# DCDC_stepdown.net
KiCad netlist of a schematic drawn in Altium Designer
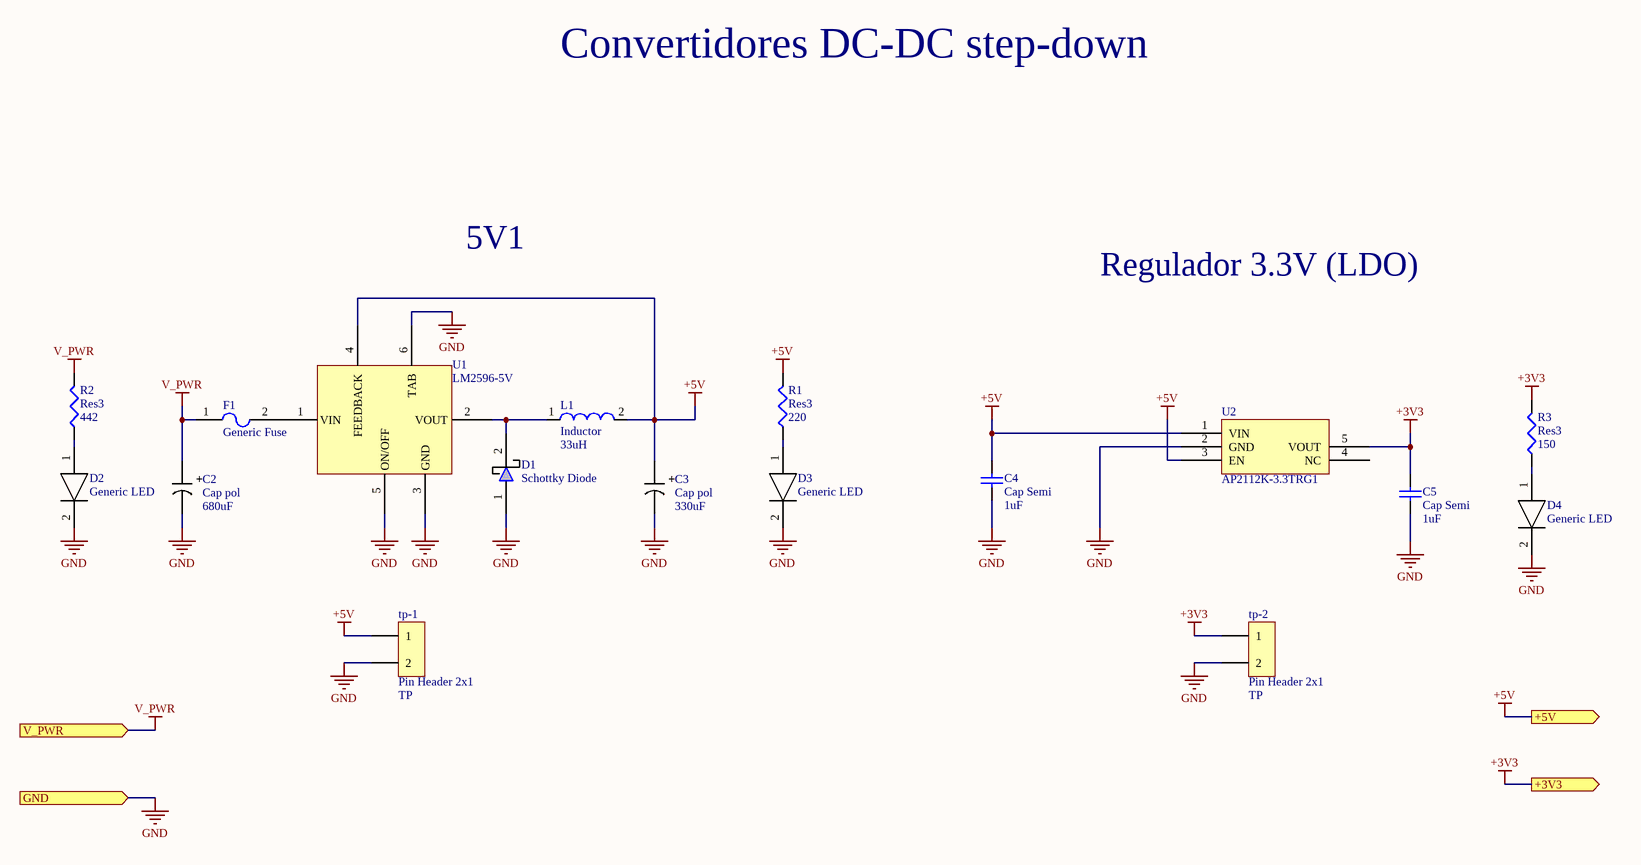
[diagram p0: DCDC_stepdown.SchDoc]

(export (version "E")
  (design (tool "Eeschema 10.0.6"))
  (components
    (comp (ref "C2")
      (value "Cap pol")
      (footprint "CAP_SMD_Electrolytic_10x10")
      (description "Electrolytic Aluminium Capacitor")
      (fields
        (field (name "MANUFACTURER") "PANASONIC")
        (field (name "MANUFACTURER PART NUMBER") "EEEFK1V681AQ")
        (field (name "ALTIUM_VALUE") "680uF")
      )
      (libsource (lib "IoWLabs") (part "Cap pol"))
    )
    (comp (ref "C3")
      (value "Cap pol")
      (footprint "CAP_SMD_Electrolytic_10x10")
      (description "Electrolytic Aluminium Capacitor")
      (fields
        (field (name "MANUFACTURER") "PANASONIC")
        (field (name "MANUFACTURER PART NUMBER") "EEE1VA331UAP")
        (field (name "ALTIUM_VALUE") "330uF")
      )
      (libsource (lib "IoWLabs") (part "Cap pol"))
    )
    (comp (ref "C4")
      (value "Cap Semi")
      (footprint "1608[0603]")
      (description "Capacitor (Semiconductor SIM Model)")
      (fields
        (field (name "ALTIUM_VALUE") "1uF")
        (field (name "MANUFACTURER") "Samsung Electro-Mechanics")
        (field (name "MANUFACTURER PART NUMBER") "CL10B105KO8NNNC")
        (field (name "PUBLISHER") "Altium Limited")
      )
      (libsource (lib "Miscellaneous Devices") (part "Cap Semi"))
    )
    (comp (ref "C5")
      (value "Cap Semi")
      (footprint "1608[0603]")
      (description "Capacitor (Semiconductor SIM Model)")
      (fields
        (field (name "ALTIUM_VALUE") "1uF")
        (field (name "MANUFACTURER") "Samsung Electro-Mechanics")
        (field (name "MANUFACTURER PART NUMBER") "CL10B105KO8NNNC")
        (field (name "PUBLISHER") "Altium Limited")
      )
      (libsource (lib "Miscellaneous Devices") (part "Cap Semi"))
    )
    (comp (ref "D1")
      (value "Schottky Diode")
      (footprint "SMB_L4.6-W3.6-LS5.3-RD")
      (description "Schottky Diodes")
      (fields
        (field (name "MANUFACTURER") "MCC(Micro Commercial Components)")
        (field (name "MANUFACTURER PART NUMBER") "SK32B-LTP")
      )
      (libsource (lib "IoWLabs") (part "Schottky Diode"))
    )
    (comp (ref "D2")
      (value "Generic LED")
      (footprint "LED0603")
      (description "Generic LED SMD")
      (libsource (lib "IoWLabs") (part "LED"))
    )
    (comp (ref "D3")
      (value "Generic LED")
      (footprint "LED0603")
      (description "Generic LED SMD")
      (libsource (lib "IoWLabs") (part "LED"))
    )
    (comp (ref "D4")
      (value "Generic LED")
      (footprint "LED0603")
      (description "Generic LED SMD")
      (libsource (lib "IoWLabs") (part "LED"))
    )
    (comp (ref "F1")
      (value "Generic Fuse")
      (footprint "F1206")
      (description "SMD Fuse")
      (fields (field (name "MANUFACTURER") "AEM") (field (name "MANUFACTURER PART NUMBER") "F1206VH4500TM"))
      (libsource (lib "IoWLabs") (part "FUSE"))
    )
    (comp (ref "L1")
      (value "Inductor")
      (footprint "IND-SMD_L12.5-W12.5_SMDRS1275")
      (description "Inductor SMD")
      (fields
        (field (name "MANUFACTURER") "GLE")
        (field (name "MANUFACTURER PART NUMBER") "GCRH127M-330MC")
        (field (name "ALTIUM_VALUE") "33uH")
      )
      (libsource (lib "IoWLabs") (part "Inductor"))
    )
    (comp (ref "R1")
      (value "Res3")
      (footprint "J1-0603")
      (description "Resistor")
      (fields
        (field (name "ALTIUM_VALUE") "220")
        (field (name "MANUFACTURER PART NUMBER") "AC0603FR-07442RL")
        (field (name "MANUFACTURER") "YAGEO")
        (field (name "PUBLISHER") "Altium Limited")
      )
      (libsource (lib "Miscellaneous Devices") (part "Res3"))
    )
    (comp (ref "R2")
      (value "Res3")
      (footprint "J1-0603")
      (description "Resistor")
      (fields
        (field (name "ALTIUM_VALUE") "442")
        (field (name "MANUFACTURER PART NUMBER") "AC0603FR-07442RL")
        (field (name "MANUFACTURER") "YAGEO")
        (field (name "PUBLISHER") "Altium Limited")
      )
      (libsource (lib "Miscellaneous Devices") (part "Res3"))
    )
    (comp (ref "R3")
      (value "Res3")
      (footprint "J1-0603")
      (description "Resistor")
      (fields
        (field (name "ALTIUM_VALUE") "150")
        (field (name "MANUFACTURER PART NUMBER") "AC0603FR-07442RL")
        (field (name "MANUFACTURER") "YAGEO")
        (field (name "PUBLISHER") "Altium Limited")
      )
      (libsource (lib "Miscellaneous Devices") (part "Res3"))
    )
    (comp (ref "tp-1")
      (value "Pin Header 2x1")
      (footprint "HDR-TH_P2.54-H-M_A2541WV-2P")
      (description "Pin Header 2pos, 1 row, 2.54 pitch")
      (fields
        (field (name "MANUFACTURER") "CJT(Changjiang Connectors)")
        (field (name "MANUFACTURER PART NUMBER") "A2541WV-2P")
      )
      (libsource (lib "IoWLabsConnectors") (part "Header - 2x1c"))
    )
    (comp (ref "tp-2")
      (value "Pin Header 2x1")
      (footprint "HDR-TH_P2.54-H-M_A2541WV-2P")
      (description "Pin Header 2pos, 1 row, 2.54 pitch")
      (fields
        (field (name "MANUFACTURER") "CJT(Changjiang Connectors)")
        (field (name "MANUFACTURER PART NUMBER") "A2541WV-2P")
      )
      (libsource (lib "IoWLabsConnectors") (part "Header - 2x1c"))
    )
    (comp (ref "U1")
      (value "LM2596-5V")
      (footprint "TO-263-5")
      (description "Step-Down Positive Fixed 1 3A 150kHz TO-263-5 DC-DC Converters RoHS")
      (fields
        (field (name "MANUFACTURER") "HTC Korea TAEJIN Tech")
        (field (name "MANUFACTURER PART NUMBER") "LM2596R-5.0")
      )
      (libsource (lib "IoWLabs") (part "LM2596-5V"))
    )
    (comp (ref "U2")
      (value "AP2112K-3.3TRG1")
      (footprint "SOT25-5")
      (description "600mA CMOS LDO REGULATOR WITH ENABLE")
      (fields (field (name "MANUFACTURER") "DIODES"))
      (libsource (lib "IoWLabs") (part "AP2112K-3.3"))
    )
  )
  (nets
    (net (code "1") (name "+3V3") (class "Default")
      (node (ref "C5") (pin "2") (pinfunction "2_2") (pintype "passive"))
      (node (ref "R3") (pin "2") (pinfunction "2_2") (pintype "passive"))
      (node (ref "U2") (pin "5") (pinfunction "VOUT_5") (pintype "passive"))
      (node (ref "tp-2") (pin "1") (pinfunction "1_1") (pintype "passive"))
    )
    (net (code "2") (name "+5V") (class "Default")
      (node (ref "C3") (pin "2") (pinfunction "2_2") (pintype "passive"))
      (node (ref "C4") (pin "2") (pinfunction "2_2") (pintype "passive"))
      (node (ref "L1") (pin "2") (pinfunction "2_2") (pintype "passive"))
      (node (ref "R1") (pin "2") (pinfunction "2_2") (pintype "passive"))
      (node (ref "U1") (pin "4") (pinfunction "FEEDBACK_4") (pintype "passive"))
      (node (ref "U2") (pin "1") (pinfunction "VIN_1") (pintype "passive"))
      (node (ref "U2") (pin "3") (pinfunction "EN_3") (pintype "passive"))
      (node (ref "tp-1") (pin "1") (pinfunction "1_1") (pintype "passive"))
    )
    (net (code "3") (name "GND") (class "Default")
      (node (ref "C2") (pin "1") (pinfunction "1_1") (pintype "passive"))
      (node (ref "C3") (pin "1") (pinfunction "1_1") (pintype "passive"))
      (node (ref "C4") (pin "1") (pinfunction "1_1") (pintype "passive"))
      (node (ref "C5") (pin "1") (pinfunction "1_1") (pintype "passive"))
      (node (ref "D1") (pin "1") (pinfunction "+_1") (pintype "passive"))
      (node (ref "D2") (pin "2") (pinfunction "2_2") (pintype "passive"))
      (node (ref "D3") (pin "2") (pinfunction "2_2") (pintype "passive"))
      (node (ref "D4") (pin "2") (pinfunction "2_2") (pintype "passive"))
      (node (ref "U1") (pin "3") (pinfunction "GND_3") (pintype "passive"))
      (node (ref "U1") (pin "5") (pinfunction "ON/OFF_5") (pintype "passive"))
      (node (ref "U1") (pin "6") (pinfunction "TAB_6") (pintype "passive"))
      (node (ref "U2") (pin "2") (pinfunction "GND_2") (pintype "passive"))
      (node (ref "tp-1") (pin "2") (pinfunction "2_2") (pintype "passive"))
      (node (ref "tp-2") (pin "2") (pinfunction "2_2") (pintype "passive"))
    )
    (net (code "4") (name "Net-(D1--)") (class "Default")
      (node (ref "D1") (pin "2") (pinfunction "-_2") (pintype "passive"))
      (node (ref "L1") (pin "1") (pinfunction "1_1") (pintype "passive"))
      (node (ref "U1") (pin "2") (pinfunction "VOUT_2") (pintype "passive"))
    )
    (net (code "5") (name "Net-(D2-Pad1)") (class "Default")
      (node (ref "D2") (pin "1") (pinfunction "1_1") (pintype "passive"))
      (node (ref "R2") (pin "1") (pinfunction "1_1") (pintype "passive"))
    )
    (net (code "6") (name "Net-(D3-Pad1)") (class "Default")
      (node (ref "D3") (pin "1") (pinfunction "1_1") (pintype "passive"))
      (node (ref "R1") (pin "1") (pinfunction "1_1") (pintype "passive"))
    )
    (net (code "7") (name "Net-(D4-Pad1)") (class "Default")
      (node (ref "D4") (pin "1") (pinfunction "1_1") (pintype "passive"))
      (node (ref "R3") (pin "1") (pinfunction "1_1") (pintype "passive"))
    )
    (net (code "8") (name "Net-(U1-VIN)") (class "Default")
      (node (ref "F1") (pin "2") (pinfunction "2_2") (pintype "passive"))
      (node (ref "U1") (pin "1") (pinfunction "VIN_1") (pintype "passive"))
    )
    (net (code "9") (name "V_PWR") (class "Default")
      (node (ref "C2") (pin "2") (pinfunction "2_2") (pintype "passive"))
      (node (ref "F1") (pin "1") (pinfunction "1_1") (pintype "passive"))
      (node (ref "R2") (pin "2") (pinfunction "2_2") (pintype "passive"))
    )
    (net (code "10") (name "unconnected-(U2-NC-Pad4)") (class "Default")
      (node (ref "U2") (pin "4") (pinfunction "NC_4") (pintype "passive"))
    )
  )
)
